# IMU_BNO085_Schematic.net
KiCad netlist of a schematic drawn in EAGLE
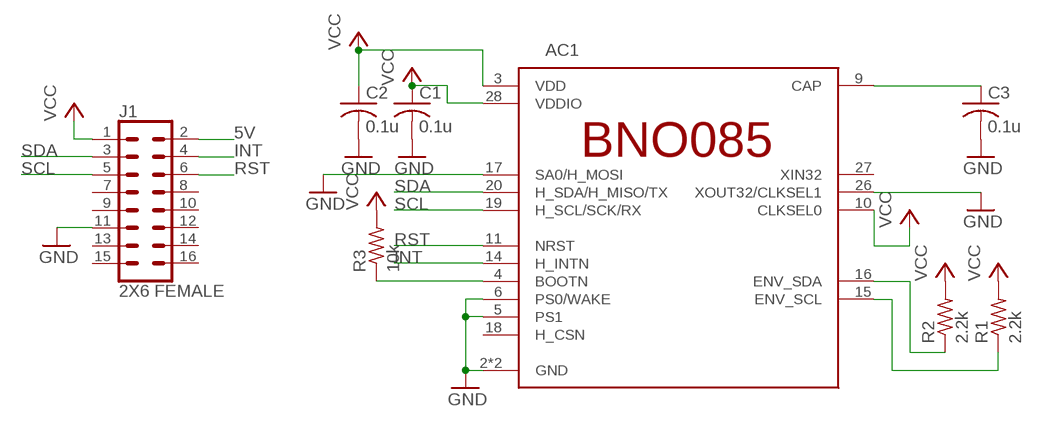
[diagram p0: schematic, sheet 1]

(export (version "E")
  (design (tool "Eeschema 10.0.6"))
  (components
    (comp (ref "AC1")
      (value "BNO085")
      (footprint "eagle-import:BNO085")
      (libsource (lib "eagle-import") (part "BNO085"))
    )
    (comp (ref "C1")
      (value "0.1u")
      (footprint "eagle-import:C1206")
      (libsource (lib "eagle-import") (part "C-ALL_PACKAGESC1206"))
    )
    (comp (ref "C2")
      (value "0.1u")
      (footprint "eagle-import:C1206")
      (libsource (lib "eagle-import") (part "C-ALL_PACKAGESC1206"))
    )
    (comp (ref "C3")
      (value "0.1u")
      (footprint "eagle-import:C1206")
      (libsource (lib "eagle-import") (part "C-ALL_PACKAGESC1206"))
    )
    (comp (ref "J1")
      (value "2X6 FEMALE")
      (footprint "eagle-import:2X7")
      (libsource (lib "eagle-import") (part "SENSOR_BREAKOUTPTH_FEMALE"))
    )
    (comp (ref "R1")
      (value "2.2k")
      (footprint "eagle-import:R1206")
      (libsource (lib "eagle-import") (part "R-ALL_PACKAGESR1206"))
    )
    (comp (ref "R2")
      (value "2.2k")
      (footprint "eagle-import:R1206")
      (libsource (lib "eagle-import") (part "R-ALL_PACKAGESR1206"))
    )
    (comp (ref "R3")
      (value "10k")
      (footprint "eagle-import:R1206")
      (libsource (lib "eagle-import") (part "R-ALL_PACKAGESR1206"))
    )
  )
  (nets
    (net (code "1") (name "/5V") (class "Default")
      (node (ref "J1") (pin "2") (pinfunction "2_2") (pintype "passive"))
    )
    (net (code "2") (name "/INT") (class "Default")
      (node (ref "AC1") (pin "14") (pinfunction "H_INTN_14") (pintype "bidirectional"))
      (node (ref "J1") (pin "4") (pinfunction "4_4") (pintype "passive"))
    )
    (net (code "3") (name "/RST") (class "Default")
      (node (ref "AC1") (pin "11") (pinfunction "NRST_11") (pintype "bidirectional"))
      (node (ref "J1") (pin "6") (pinfunction "6_6") (pintype "passive"))
    )
    (net (code "4") (name "/SCL") (class "Default")
      (node (ref "AC1") (pin "19") (pinfunction "H_SCL/SCK/RX_19") (pintype "bidirectional"))
      (node (ref "J1") (pin "5") (pinfunction "5_5") (pintype "passive"))
    )
    (net (code "5") (name "/SDA") (class "Default")
      (node (ref "AC1") (pin "20") (pinfunction "H_SDA/H_MISO/TX_20") (pintype "bidirectional"))
      (node (ref "J1") (pin "3") (pinfunction "3_3") (pintype "passive"))
    )
    (net (code "6") (name "GND") (class "Default")
      (node (ref "AC1") (pin "17") (pinfunction "SA0/H_MOSI_17") (pintype "bidirectional"))
      (node (ref "AC1") (pin "2") (pinfunction "GND_2") (pintype "bidirectional"))
      (node (ref "AC1") (pin "25") (pinfunction "GND_25") (pintype "bidirectional"))
      (node (ref "AC1") (pin "26") (pinfunction "XOUT32/CLKSEL1_26") (pintype "bidirectional"))
      (node (ref "AC1") (pin "5") (pinfunction "PS1_5") (pintype "bidirectional"))
      (node (ref "AC1") (pin "6") (pinfunction "PS0/WAKE_6") (pintype "bidirectional"))
      (node (ref "C1") (pin "2") (pinfunction "2_2") (pintype "passive"))
      (node (ref "C2") (pin "2") (pinfunction "2_2") (pintype "passive"))
      (node (ref "C3") (pin "2") (pinfunction "2_2") (pintype "passive"))
      (node (ref "J1") (pin "11") (pinfunction "11_11") (pintype "passive"))
    )
    (net (code "7") (name "Net-(AC1-BOOTN)") (class "Default")
      (node (ref "AC1") (pin "4") (pinfunction "BOOTN_4") (pintype "bidirectional"))
      (node (ref "R3") (pin "1") (pinfunction "1_1") (pintype "passive"))
    )
    (net (code "8") (name "Net-(AC1-CAP)") (class "Default")
      (node (ref "AC1") (pin "9") (pinfunction "CAP_9") (pintype "bidirectional"))
      (node (ref "C3") (pin "1") (pinfunction "1_1") (pintype "passive"))
    )
    (net (code "9") (name "Net-(AC1-ENV_SCL)") (class "Default")
      (node (ref "AC1") (pin "15") (pinfunction "ENV_SCL_15") (pintype "bidirectional"))
      (node (ref "R1") (pin "1") (pinfunction "1_1") (pintype "passive"))
    )
    (net (code "10") (name "Net-(AC1-ENV_SDA)") (class "Default")
      (node (ref "AC1") (pin "16") (pinfunction "ENV_SDA_16") (pintype "bidirectional"))
      (node (ref "R2") (pin "1") (pinfunction "1_1") (pintype "passive"))
    )
    (net (code "11") (name "VCC") (class "Default")
      (node (ref "AC1") (pin "10") (pinfunction "CLKSEL0_10") (pintype "bidirectional"))
      (node (ref "AC1") (pin "28") (pinfunction "VDDIO_28") (pintype "bidirectional"))
      (node (ref "AC1") (pin "3") (pinfunction "VDD_3") (pintype "bidirectional"))
      (node (ref "C1") (pin "1") (pinfunction "1_1") (pintype "passive"))
      (node (ref "C2") (pin "1") (pinfunction "1_1") (pintype "passive"))
      (node (ref "J1") (pin "1") (pinfunction "1_1") (pintype "passive"))
      (node (ref "R1") (pin "2") (pinfunction "2_2") (pintype "passive"))
      (node (ref "R2") (pin "2") (pinfunction "2_2") (pintype "passive"))
      (node (ref "R3") (pin "2") (pinfunction "2_2") (pintype "passive"))
    )
    (net (code "12") (name "unconnected-(AC1-H_CSN-Pad18)") (class "Default")
      (node (ref "AC1") (pin "18") (pinfunction "H_CSN_18") (pintype "bidirectional"))
    )
    (net (code "13") (name "unconnected-(AC1-XIN32-Pad27)") (class "Default")
      (node (ref "AC1") (pin "27") (pinfunction "XIN32_27") (pintype "bidirectional"))
    )
    (net (code "14") (name "unconnected-(J1-Pad7)") (class "Default")
      (node (ref "J1") (pin "7") (pinfunction "7_7") (pintype "passive"))
    )
    (net (code "15") (name "unconnected-(J1-Pad8)") (class "Default")
      (node (ref "J1") (pin "8") (pinfunction "8_8") (pintype "passive"))
    )
    (net (code "16") (name "unconnected-(J1-Pad9)") (class "Default")
      (node (ref "J1") (pin "9") (pinfunction "9_9") (pintype "passive"))
    )
    (net (code "17") (name "unconnected-(J1-Pad10)") (class "Default")
      (node (ref "J1") (pin "10") (pinfunction "10_10") (pintype "passive"))
    )
    (net (code "18") (name "unconnected-(J1-Pad12)") (class "Default")
      (node (ref "J1") (pin "12") (pinfunction "12_12") (pintype "passive"))
    )
    (net (code "19") (name "unconnected-(J1-Pad13)") (class "Default")
      (node (ref "J1") (pin "13") (pinfunction "13_13") (pintype "passive"))
    )
    (net (code "20") (name "unconnected-(J1-Pad14)") (class "Default")
      (node (ref "J1") (pin "14") (pinfunction "14_14") (pintype "passive"))
    )
    (net (code "21") (name "unconnected-(J1-Pad15)") (class "Default")
      (node (ref "J1") (pin "15") (pinfunction "15_15") (pintype "passive"))
    )
    (net (code "22") (name "unconnected-(J1-Pad16)") (class "Default")
      (node (ref "J1") (pin "16") (pinfunction "16_16") (pintype "passive"))
    )
  )
)
